# V3.net
KiCad netlist of a schematic drawn in Altium Designer
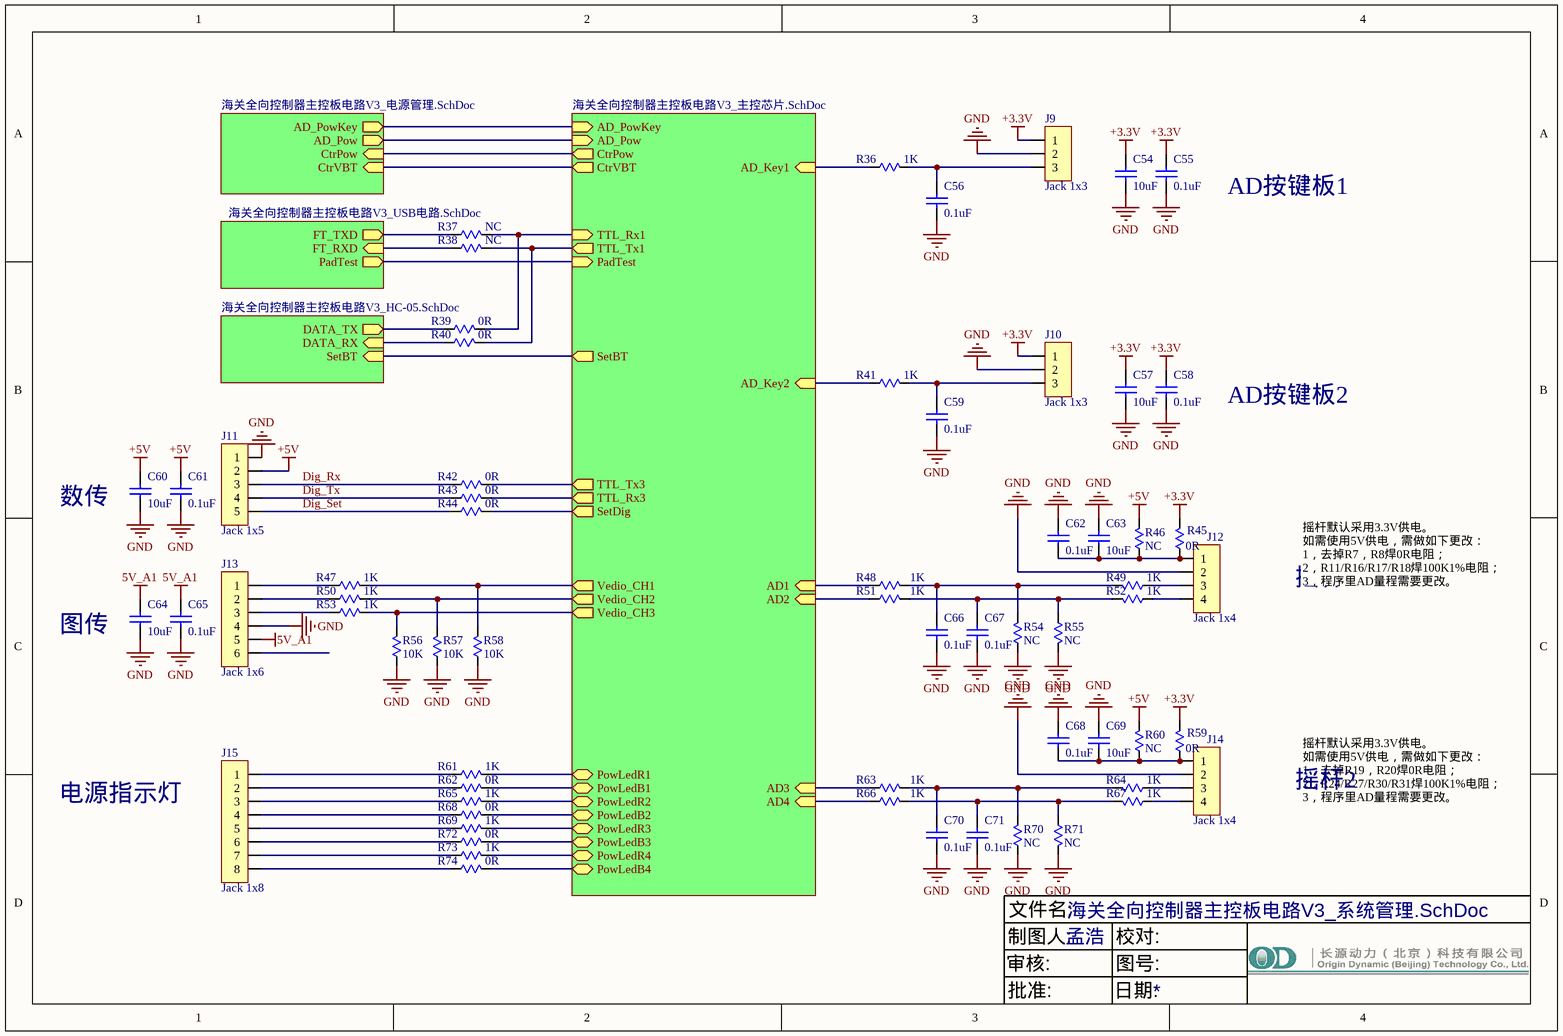
[diagram p0: 海关全向控制器主控板电路V3_系统管理.SchDoc]

(export (version "E")
  (design (tool "Eeschema 10.0.6"))
  (components
    (comp (ref "C54")
      (value "10uF")
      (footprint "C0805")
      (description "Capacitor")
      (fields (field (name "PUBLISHER") "Altium Limited"))
      (libsource (lib "Miscellaneous Devices") (part "Cap"))
    )
    (comp (ref "C55")
      (value "0.1uF")
      (footprint "C0805")
      (description "Capacitor")
      (fields (field (name "PUBLISHER") "Altium Limited"))
      (libsource (lib "Miscellaneous Devices") (part "Cap"))
    )
    (comp (ref "C56")
      (value "0.1uF")
      (footprint "C0805")
      (description "Capacitor")
      (fields (field (name "PUBLISHER") "Altium Limited"))
      (libsource (lib "Miscellaneous Devices") (part "Cap"))
    )
    (comp (ref "C57")
      (value "10uF")
      (footprint "C0805")
      (description "Capacitor")
      (fields (field (name "PUBLISHER") "Altium Limited"))
      (libsource (lib "Miscellaneous Devices") (part "Cap"))
    )
    (comp (ref "C58")
      (value "0.1uF")
      (footprint "C0805")
      (description "Capacitor")
      (fields (field (name "PUBLISHER") "Altium Limited"))
      (libsource (lib "Miscellaneous Devices") (part "Cap"))
    )
    (comp (ref "C59")
      (value "0.1uF")
      (footprint "C0805")
      (description "Capacitor")
      (fields (field (name "PUBLISHER") "Altium Limited"))
      (libsource (lib "Miscellaneous Devices") (part "Cap"))
    )
    (comp (ref "C60")
      (value "10uF")
      (footprint "C0805")
      (description "Capacitor")
      (fields (field (name "PUBLISHER") "Altium Limited"))
      (libsource (lib "Miscellaneous Devices") (part "Cap"))
    )
    (comp (ref "C61")
      (value "0.1uF")
      (footprint "C0805")
      (description "Capacitor")
      (fields (field (name "PUBLISHER") "Altium Limited"))
      (libsource (lib "Miscellaneous Devices") (part "Cap"))
    )
    (comp (ref "C62")
      (value "0.1uF")
      (footprint "C0805")
      (description "Capacitor")
      (fields (field (name "PUBLISHER") "Altium Limited"))
      (libsource (lib "Miscellaneous Devices") (part "Cap"))
    )
    (comp (ref "C63")
      (value "10uF")
      (footprint "C0805")
      (description "Capacitor")
      (fields (field (name "PUBLISHER") "Altium Limited"))
      (libsource (lib "Miscellaneous Devices") (part "Cap"))
    )
    (comp (ref "C64")
      (value "10uF")
      (footprint "C0805")
      (description "Capacitor")
      (fields (field (name "PUBLISHER") "Altium Limited"))
      (libsource (lib "Miscellaneous Devices") (part "Cap"))
    )
    (comp (ref "C65")
      (value "0.1uF")
      (footprint "C0805")
      (description "Capacitor")
      (fields (field (name "PUBLISHER") "Altium Limited"))
      (libsource (lib "Miscellaneous Devices") (part "Cap"))
    )
    (comp (ref "C66")
      (value "0.1uF")
      (footprint "C0805")
      (description "Capacitor")
      (fields (field (name "PUBLISHER") "Altium Limited"))
      (libsource (lib "Miscellaneous Devices") (part "Cap"))
    )
    (comp (ref "C67")
      (value "0.1uF")
      (footprint "C0805")
      (description "Capacitor")
      (fields (field (name "PUBLISHER") "Altium Limited"))
      (libsource (lib "Miscellaneous Devices") (part "Cap"))
    )
    (comp (ref "C68")
      (value "0.1uF")
      (footprint "C0805")
      (description "Capacitor")
      (fields (field (name "PUBLISHER") "Altium Limited"))
      (libsource (lib "Miscellaneous Devices") (part "Cap"))
    )
    (comp (ref "C69")
      (value "10uF")
      (footprint "C0805")
      (description "Capacitor")
      (fields (field (name "PUBLISHER") "Altium Limited"))
      (libsource (lib "Miscellaneous Devices") (part "Cap"))
    )
    (comp (ref "C70")
      (value "0.1uF")
      (footprint "C0805")
      (description "Capacitor")
      (fields (field (name "PUBLISHER") "Altium Limited"))
      (libsource (lib "Miscellaneous Devices") (part "Cap"))
    )
    (comp (ref "C71")
      (value "0.1uF")
      (footprint "C0805")
      (description "Capacitor")
      (fields (field (name "PUBLISHER") "Altium Limited"))
      (libsource (lib "Miscellaneous Devices") (part "Cap"))
    )
    (comp (ref "J9")
      (value "Jack 1x3")
      (footprint "ZH-3AWD")
      (description "插座")
      (libsource (lib "Connector") (part "Jack 1x3"))
    )
    (comp (ref "J10")
      (value "Jack 1x3")
      (footprint "ZH-3AWD")
      (description "插座")
      (libsource (lib "Connector") (part "Jack 1x3"))
    )
    (comp (ref "J11")
      (value "Jack 1x5")
      (footprint "ZH-5AWD")
      (description "插座")
      (libsource (lib "Connector") (part "Jack 1x5"))
    )
    (comp (ref "J12")
      (value "Jack 1x4")
      (footprint "ZH-4AWD")
      (description "插座")
      (libsource (lib "Connector") (part "Jack 1x4"))
    )
    (comp (ref "J13")
      (value "Jack 1x6")
      (footprint "ZH-6AWD")
      (description "插座")
      (libsource (lib "Connector") (part "Jack 1x6"))
    )
    (comp (ref "J14")
      (value "Jack 1x4")
      (footprint "ZH-4AWD")
      (description "插座")
      (libsource (lib "Connector") (part "Jack 1x4"))
    )
    (comp (ref "J15")
      (value "Jack 1x8")
      (footprint "ZH-8AWD")
      (description "插座")
      (libsource (lib "Connector") (part "Jack 1x8"))
    )
    (comp (ref "R36")
      (value "1K")
      (footprint "R0805")
      (description "Resistor")
      (fields (field (name "PUBLISHER") "Altium Limited"))
      (libsource (lib "UP-Robot") (part "Res"))
    )
    (comp (ref "R37")
      (value "NC")
      (footprint "R0805")
      (description "Resistor")
      (fields (field (name "PUBLISHER") "Altium Limited"))
      (libsource (lib "Temp") (part "Res"))
    )
    (comp (ref "R38")
      (value "NC")
      (footprint "R0805")
      (description "Resistor")
      (fields (field (name "PUBLISHER") "Altium Limited"))
      (libsource (lib "Temp") (part "Res"))
    )
    (comp (ref "R39")
      (value "0R")
      (footprint "R0805")
      (description "Resistor")
      (fields (field (name "PUBLISHER") "Altium Limited"))
      (libsource (lib "Temp") (part "Res"))
    )
    (comp (ref "R40")
      (value "0R")
      (footprint "R0805")
      (description "Resistor")
      (fields (field (name "PUBLISHER") "Altium Limited"))
      (libsource (lib "Temp") (part "Res"))
    )
    (comp (ref "R41")
      (value "1K")
      (footprint "R0805")
      (description "Resistor")
      (fields (field (name "PUBLISHER") "Altium Limited"))
      (libsource (lib "UP-Robot") (part "Res"))
    )
    (comp (ref "R42")
      (value "0R")
      (footprint "R0805")
      (description "Resistor")
      (fields (field (name "PUBLISHER") "Altium Limited"))
      (libsource (lib "UP-Robot") (part "Res"))
    )
    (comp (ref "R43")
      (value "0R")
      (footprint "R0805")
      (description "Resistor")
      (fields (field (name "PUBLISHER") "Altium Limited"))
      (libsource (lib "UP-Robot") (part "Res"))
    )
    (comp (ref "R44")
      (value "0R")
      (footprint "R0805")
      (description "Resistor")
      (fields (field (name "PUBLISHER") "Altium Limited"))
      (libsource (lib "UP-Robot") (part "Res"))
    )
    (comp (ref "R45")
      (value "0R")
      (footprint "R0805")
      (description "Resistor")
      (fields (field (name "PUBLISHER") "Altium Limited"))
      (libsource (lib "UP-Robot") (part "Res"))
    )
    (comp (ref "R46")
      (value "NC")
      (footprint "R0805")
      (description "Resistor")
      (fields (field (name "PUBLISHER") "Altium Limited"))
      (libsource (lib "UP-Robot") (part "Res"))
    )
    (comp (ref "R47")
      (value "1K")
      (footprint "R0805")
      (description "Resistor")
      (fields (field (name "PUBLISHER") "Altium Limited"))
      (libsource (lib "UP-Robot") (part "Res"))
    )
    (comp (ref "R48")
      (value "1K")
      (footprint "R0805")
      (description "Resistor")
      (fields (field (name "PUBLISHER") "Altium Limited"))
      (libsource (lib "UP-Robot") (part "Res"))
    )
    (comp (ref "R49")
      (value "1K")
      (footprint "R0805")
      (description "Resistor")
      (fields (field (name "PUBLISHER") "Altium Limited"))
      (libsource (lib "UP-Robot") (part "Res"))
    )
    (comp (ref "R50")
      (value "1K")
      (footprint "R0805")
      (description "Resistor")
      (fields (field (name "PUBLISHER") "Altium Limited"))
      (libsource (lib "UP-Robot") (part "Res"))
    )
    (comp (ref "R51")
      (value "1K")
      (footprint "R0805")
      (description "Resistor")
      (fields (field (name "PUBLISHER") "Altium Limited"))
      (libsource (lib "UP-Robot") (part "Res"))
    )
    (comp (ref "R52")
      (value "1K")
      (footprint "R0805")
      (description "Resistor")
      (fields (field (name "PUBLISHER") "Altium Limited"))
      (libsource (lib "UP-Robot") (part "Res"))
    )
    (comp (ref "R53")
      (value "1K")
      (footprint "R0805")
      (description "Resistor")
      (fields (field (name "PUBLISHER") "Altium Limited"))
      (libsource (lib "UP-Robot") (part "Res"))
    )
    (comp (ref "R54")
      (value "NC")
      (footprint "R0805")
      (description "Resistor")
      (fields (field (name "PUBLISHER") "Altium Limited"))
      (libsource (lib "UP-Robot") (part "Res"))
    )
    (comp (ref "R55")
      (value "NC")
      (footprint "R0805")
      (description "Resistor")
      (fields (field (name "PUBLISHER") "Altium Limited"))
      (libsource (lib "UP-Robot") (part "Res"))
    )
    (comp (ref "R56")
      (value "10K")
      (footprint "R0805")
      (description "Resistor")
      (fields (field (name "PUBLISHER") "Altium Limited"))
      (libsource (lib "UP-Robot") (part "Res"))
    )
    (comp (ref "R57")
      (value "10K")
      (footprint "R0805")
      (description "Resistor")
      (fields (field (name "PUBLISHER") "Altium Limited"))
      (libsource (lib "UP-Robot") (part "Res"))
    )
    (comp (ref "R58")
      (value "10K")
      (footprint "R0805")
      (description "Resistor")
      (fields (field (name "PUBLISHER") "Altium Limited"))
      (libsource (lib "UP-Robot") (part "Res"))
    )
    (comp (ref "R59")
      (value "0R")
      (footprint "R0805")
      (description "Resistor")
      (fields (field (name "PUBLISHER") "Altium Limited"))
      (libsource (lib "UP-Robot") (part "Res"))
    )
    (comp (ref "R60")
      (value "NC")
      (footprint "R0805")
      (description "Resistor")
      (fields (field (name "PUBLISHER") "Altium Limited"))
      (libsource (lib "UP-Robot") (part "Res"))
    )
    (comp (ref "R61")
      (value "1K")
      (footprint "R0805")
      (description "Resistor")
      (fields (field (name "PUBLISHER") "Altium Limited"))
      (libsource (lib "UP-Robot") (part "Res"))
    )
    (comp (ref "R62")
      (value "0R")
      (footprint "R0805")
      (description "Resistor")
      (fields (field (name "PUBLISHER") "Altium Limited"))
      (libsource (lib "UP-Robot") (part "Res"))
    )
    (comp (ref "R63")
      (value "1K")
      (footprint "R0805")
      (description "Resistor")
      (fields (field (name "PUBLISHER") "Altium Limited"))
      (libsource (lib "UP-Robot") (part "Res"))
    )
    (comp (ref "R64")
      (value "1K")
      (footprint "R0805")
      (description "Resistor")
      (fields (field (name "PUBLISHER") "Altium Limited"))
      (libsource (lib "UP-Robot") (part "Res"))
    )
    (comp (ref "R65")
      (value "1K")
      (footprint "R0805")
      (description "Resistor")
      (fields (field (name "PUBLISHER") "Altium Limited"))
      (libsource (lib "UP-Robot") (part "Res"))
    )
    (comp (ref "R66")
      (value "1K")
      (footprint "R0805")
      (description "Resistor")
      (fields (field (name "PUBLISHER") "Altium Limited"))
      (libsource (lib "UP-Robot") (part "Res"))
    )
    (comp (ref "R67")
      (value "1K")
      (footprint "R0805")
      (description "Resistor")
      (fields (field (name "PUBLISHER") "Altium Limited"))
      (libsource (lib "UP-Robot") (part "Res"))
    )
    (comp (ref "R68")
      (value "0R")
      (footprint "R0805")
      (description "Resistor")
      (fields (field (name "PUBLISHER") "Altium Limited"))
      (libsource (lib "UP-Robot") (part "Res"))
    )
    (comp (ref "R69")
      (value "1K")
      (footprint "R0805")
      (description "Resistor")
      (fields (field (name "PUBLISHER") "Altium Limited"))
      (libsource (lib "UP-Robot") (part "Res"))
    )
    (comp (ref "R70")
      (value "NC")
      (footprint "R0805")
      (description "Resistor")
      (fields (field (name "PUBLISHER") "Altium Limited"))
      (libsource (lib "UP-Robot") (part "Res"))
    )
    (comp (ref "R71")
      (value "NC")
      (footprint "R0805")
      (description "Resistor")
      (fields (field (name "PUBLISHER") "Altium Limited"))
      (libsource (lib "UP-Robot") (part "Res"))
    )
    (comp (ref "R72")
      (value "0R")
      (footprint "R0805")
      (description "Resistor")
      (fields (field (name "PUBLISHER") "Altium Limited"))
      (libsource (lib "UP-Robot") (part "Res"))
    )
    (comp (ref "R73")
      (value "1K")
      (footprint "R0805")
      (description "Resistor")
      (fields (field (name "PUBLISHER") "Altium Limited"))
      (libsource (lib "UP-Robot") (part "Res"))
    )
    (comp (ref "R74")
      (value "0R")
      (footprint "R0805")
      (description "Resistor")
      (fields (field (name "PUBLISHER") "Altium Limited"))
      (libsource (lib "UP-Robot") (part "Res"))
    )
  )
  (nets
    (net (code "1") (name "+3.3V") (class "Default")
      (node (ref "C54") (pin "1") (pinfunction "1_1") (pintype "passive"))
      (node (ref "C55") (pin "1") (pinfunction "1_1") (pintype "passive"))
      (node (ref "C57") (pin "1") (pinfunction "1_1") (pintype "passive"))
      (node (ref "C58") (pin "1") (pinfunction "1_1") (pintype "passive"))
      (node (ref "J10") (pin "1") (pinfunction "1_1") (pintype "passive"))
      (node (ref "J9") (pin "1") (pinfunction "1_1") (pintype "passive"))
      (node (ref "R45") (pin "1") (pinfunction "1_1") (pintype "passive"))
      (node (ref "R59") (pin "1") (pinfunction "1_1") (pintype "passive"))
    )
    (net (code "2") (name "+5V") (class "Default")
      (node (ref "C60") (pin "1") (pinfunction "1_1") (pintype "passive"))
      (node (ref "C61") (pin "1") (pinfunction "1_1") (pintype "passive"))
      (node (ref "J11") (pin "2") (pinfunction "2_2") (pintype "passive"))
      (node (ref "R46") (pin "1") (pinfunction "1_1") (pintype "passive"))
      (node (ref "R60") (pin "1") (pinfunction "1_1") (pintype "passive"))
    )
    (net (code "3") (name "/AD1") (class "Default")
      (node (ref "R48") (pin "2") (pinfunction "2_2") (pintype "passive"))
    )
    (net (code "4") (name "/AD2") (class "Default")
      (node (ref "R51") (pin "2") (pinfunction "2_2") (pintype "passive"))
    )
    (net (code "5") (name "/AD3") (class "Default")
      (node (ref "R63") (pin "2") (pinfunction "2_2") (pintype "passive"))
    )
    (net (code "6") (name "/AD4") (class "Default")
      (node (ref "R66") (pin "2") (pinfunction "2_2") (pintype "passive"))
    )
    (net (code "7") (name "/AD_Key1") (class "Default")
      (node (ref "R36") (pin "1") (pinfunction "1_1") (pintype "passive"))
    )
    (net (code "8") (name "/AD_Key2") (class "Default")
      (node (ref "R41") (pin "1") (pinfunction "1_1") (pintype "passive"))
    )
    (net (code "13") (name "/DATA_RX") (class "Default")
      (node (ref "R40") (pin "2") (pinfunction "2_2") (pintype "passive"))
    )
    (net (code "14") (name "/DATA_TX") (class "Default")
      (node (ref "R39") (pin "2") (pinfunction "2_2") (pintype "passive"))
    )
    (net (code "15") (name "/Dig_Rx") (class "Default")
      (node (ref "J11") (pin "3") (pinfunction "3_3") (pintype "passive"))
      (node (ref "R42") (pin "1") (pinfunction "1_1") (pintype "passive"))
    )
    (net (code "16") (name "/Dig_Set") (class "Default")
      (node (ref "J11") (pin "5") (pinfunction "5_5") (pintype "passive"))
      (node (ref "R44") (pin "1") (pinfunction "1_1") (pintype "passive"))
    )
    (net (code "17") (name "/Dig_Tx") (class "Default")
      (node (ref "J11") (pin "4") (pinfunction "4_4") (pintype "passive"))
      (node (ref "R43") (pin "1") (pinfunction "1_1") (pintype "passive"))
    )
    (net (code "18") (name "/FT_RXD") (class "Default")
      (node (ref "R38") (pin "2") (pinfunction "2_2") (pintype "passive"))
    )
    (net (code "19") (name "/FT_TXD") (class "Default")
      (node (ref "R37") (pin "2") (pinfunction "2_2") (pintype "passive"))
    )
    (net (code "21") (name "/PowLedB1") (class "Default")
      (node (ref "R62") (pin "2") (pinfunction "2_2") (pintype "passive"))
    )
    (net (code "22") (name "/PowLedB2") (class "Default")
      (node (ref "R68") (pin "2") (pinfunction "2_2") (pintype "passive"))
    )
    (net (code "23") (name "/PowLedB3") (class "Default")
      (node (ref "R72") (pin "2") (pinfunction "2_2") (pintype "passive"))
    )
    (net (code "24") (name "/PowLedB4") (class "Default")
      (node (ref "R74") (pin "2") (pinfunction "2_2") (pintype "passive"))
    )
    (net (code "25") (name "/PowLedR1") (class "Default")
      (node (ref "R61") (pin "2") (pinfunction "2_2") (pintype "passive"))
    )
    (net (code "26") (name "/PowLedR2") (class "Default")
      (node (ref "R65") (pin "2") (pinfunction "2_2") (pintype "passive"))
    )
    (net (code "27") (name "/PowLedR3") (class "Default")
      (node (ref "R69") (pin "2") (pinfunction "2_2") (pintype "passive"))
    )
    (net (code "28") (name "/PowLedR4") (class "Default")
      (node (ref "R73") (pin "2") (pinfunction "2_2") (pintype "passive"))
    )
    (net (code "30") (name "/SetDig") (class "Default")
      (node (ref "R44") (pin "2") (pinfunction "2_2") (pintype "passive"))
    )
    (net (code "31") (name "/TTL_Rx1") (class "Default")
      (node (ref "R37") (pin "1") (pinfunction "1_1") (pintype "passive"))
      (node (ref "R39") (pin "1") (pinfunction "1_1") (pintype "passive"))
    )
    (net (code "32") (name "/TTL_Rx3") (class "Default")
      (node (ref "R43") (pin "2") (pinfunction "2_2") (pintype "passive"))
    )
    (net (code "33") (name "/TTL_Tx1") (class "Default")
      (node (ref "R38") (pin "1") (pinfunction "1_1") (pintype "passive"))
      (node (ref "R40") (pin "1") (pinfunction "1_1") (pintype "passive"))
    )
    (net (code "34") (name "/TTL_Tx3") (class "Default")
      (node (ref "R42") (pin "2") (pinfunction "2_2") (pintype "passive"))
    )
    (net (code "35") (name "/Vedio_CH1") (class "Default")
      (node (ref "R47") (pin "2") (pinfunction "2_2") (pintype "passive"))
      (node (ref "R58") (pin "2") (pinfunction "2_2") (pintype "passive"))
    )
    (net (code "36") (name "/Vedio_CH2") (class "Default")
      (node (ref "R50") (pin "2") (pinfunction "2_2") (pintype "passive"))
      (node (ref "R57") (pin "2") (pinfunction "2_2") (pintype "passive"))
    )
    (net (code "37") (name "/Vedio_CH3") (class "Default")
      (node (ref "R53") (pin "2") (pinfunction "2_2") (pintype "passive"))
      (node (ref "R56") (pin "2") (pinfunction "2_2") (pintype "passive"))
    )
    (net (code "38") (name "5V_A1") (class "Default")
      (node (ref "C64") (pin "1") (pinfunction "1_1") (pintype "passive"))
      (node (ref "C65") (pin "1") (pinfunction "1_1") (pintype "passive"))
      (node (ref "J13") (pin "5") (pinfunction "5_5") (pintype "passive"))
    )
    (net (code "39") (name "GND") (class "Default")
      (node (ref "C54") (pin "2") (pinfunction "2_2") (pintype "passive"))
      (node (ref "C55") (pin "2") (pinfunction "2_2") (pintype "passive"))
      (node (ref "C56") (pin "2") (pinfunction "2_2") (pintype "passive"))
      (node (ref "C57") (pin "2") (pinfunction "2_2") (pintype "passive"))
      (node (ref "C58") (pin "2") (pinfunction "2_2") (pintype "passive"))
      (node (ref "C59") (pin "2") (pinfunction "2_2") (pintype "passive"))
      (node (ref "C60") (pin "2") (pinfunction "2_2") (pintype "passive"))
      (node (ref "C61") (pin "2") (pinfunction "2_2") (pintype "passive"))
      (node (ref "C62") (pin "1") (pinfunction "1_1") (pintype "passive"))
      (node (ref "C63") (pin "1") (pinfunction "1_1") (pintype "passive"))
      (node (ref "C64") (pin "2") (pinfunction "2_2") (pintype "passive"))
      (node (ref "C65") (pin "2") (pinfunction "2_2") (pintype "passive"))
      (node (ref "C66") (pin "2") (pinfunction "2_2") (pintype "passive"))
      (node (ref "C67") (pin "2") (pinfunction "2_2") (pintype "passive"))
      (node (ref "C68") (pin "1") (pinfunction "1_1") (pintype "passive"))
      (node (ref "C69") (pin "1") (pinfunction "1_1") (pintype "passive"))
      (node (ref "C70") (pin "2") (pinfunction "2_2") (pintype "passive"))
      (node (ref "C71") (pin "2") (pinfunction "2_2") (pintype "passive"))
      (node (ref "J10") (pin "2") (pinfunction "2_2") (pintype "passive"))
      (node (ref "J11") (pin "1") (pinfunction "1_1") (pintype "passive"))
      (node (ref "J12") (pin "2") (pinfunction "2_2") (pintype "passive"))
      (node (ref "J13") (pin "4") (pinfunction "4_4") (pintype "passive"))
      (node (ref "J14") (pin "2") (pinfunction "2_2") (pintype "passive"))
      (node (ref "J9") (pin "2") (pinfunction "2_2") (pintype "passive"))
      (node (ref "R54") (pin "2") (pinfunction "2_2") (pintype "passive"))
      (node (ref "R55") (pin "1") (pinfunction "1_1") (pintype "passive"))
      (node (ref "R56") (pin "1") (pinfunction "1_1") (pintype "passive"))
      (node (ref "R57") (pin "1") (pinfunction "1_1") (pintype "passive"))
      (node (ref "R58") (pin "1") (pinfunction "1_1") (pintype "passive"))
      (node (ref "R70") (pin "2") (pinfunction "2_2") (pintype "passive"))
      (node (ref "R71") (pin "1") (pinfunction "1_1") (pintype "passive"))
    )
    (net (code "40") (name "Net-(C56-Pad1)") (class "Default")
      (node (ref "C56") (pin "1") (pinfunction "1_1") (pintype "passive"))
      (node (ref "J9") (pin "3") (pinfunction "3_3") (pintype "passive"))
      (node (ref "R36") (pin "2") (pinfunction "2_2") (pintype "passive"))
    )
    (net (code "41") (name "Net-(C59-Pad1)") (class "Default")
      (node (ref "C59") (pin "1") (pinfunction "1_1") (pintype "passive"))
      (node (ref "J10") (pin "3") (pinfunction "3_3") (pintype "passive"))
      (node (ref "R41") (pin "2") (pinfunction "2_2") (pintype "passive"))
    )
    (net (code "42") (name "Net-(C62-Pad2)") (class "Default")
      (node (ref "C62") (pin "2") (pinfunction "2_2") (pintype "passive"))
      (node (ref "C63") (pin "2") (pinfunction "2_2") (pintype "passive"))
      (node (ref "J12") (pin "1") (pinfunction "1_1") (pintype "passive"))
      (node (ref "R45") (pin "2") (pinfunction "2_2") (pintype "passive"))
      (node (ref "R46") (pin "2") (pinfunction "2_2") (pintype "passive"))
    )
    (net (code "43") (name "Net-(C66-Pad1)") (class "Default")
      (node (ref "C66") (pin "1") (pinfunction "1_1") (pintype "passive"))
      (node (ref "R48") (pin "1") (pinfunction "1_1") (pintype "passive"))
      (node (ref "R49") (pin "1") (pinfunction "1_1") (pintype "passive"))
      (node (ref "R54") (pin "1") (pinfunction "1_1") (pintype "passive"))
    )
    (net (code "44") (name "Net-(C67-Pad1)") (class "Default")
      (node (ref "C67") (pin "1") (pinfunction "1_1") (pintype "passive"))
      (node (ref "R51") (pin "1") (pinfunction "1_1") (pintype "passive"))
      (node (ref "R52") (pin "1") (pinfunction "1_1") (pintype "passive"))
      (node (ref "R55") (pin "2") (pinfunction "2_2") (pintype "passive"))
    )
    (net (code "45") (name "Net-(C68-Pad2)") (class "Default")
      (node (ref "C68") (pin "2") (pinfunction "2_2") (pintype "passive"))
      (node (ref "C69") (pin "2") (pinfunction "2_2") (pintype "passive"))
      (node (ref "J14") (pin "1") (pinfunction "1_1") (pintype "passive"))
      (node (ref "R59") (pin "2") (pinfunction "2_2") (pintype "passive"))
      (node (ref "R60") (pin "2") (pinfunction "2_2") (pintype "passive"))
    )
    (net (code "46") (name "Net-(C70-Pad1)") (class "Default")
      (node (ref "C70") (pin "1") (pinfunction "1_1") (pintype "passive"))
      (node (ref "R63") (pin "1") (pinfunction "1_1") (pintype "passive"))
      (node (ref "R64") (pin "1") (pinfunction "1_1") (pintype "passive"))
      (node (ref "R70") (pin "1") (pinfunction "1_1") (pintype "passive"))
    )
    (net (code "47") (name "Net-(C71-Pad1)") (class "Default")
      (node (ref "C71") (pin "1") (pinfunction "1_1") (pintype "passive"))
      (node (ref "R66") (pin "1") (pinfunction "1_1") (pintype "passive"))
      (node (ref "R67") (pin "1") (pinfunction "1_1") (pintype "passive"))
      (node (ref "R71") (pin "2") (pinfunction "2_2") (pintype "passive"))
    )
    (net (code "48") (name "Net-(J12-Pad3)") (class "Default")
      (node (ref "J12") (pin "3") (pinfunction "3_3") (pintype "passive"))
      (node (ref "R49") (pin "2") (pinfunction "2_2") (pintype "passive"))
    )
    (net (code "49") (name "Net-(J12-Pad4)") (class "Default")
      (node (ref "J12") (pin "4") (pinfunction "4_4") (pintype "passive"))
      (node (ref "R52") (pin "2") (pinfunction "2_2") (pintype "passive"))
    )
    (net (code "50") (name "Net-(J13-Pad1)") (class "Default")
      (node (ref "J13") (pin "1") (pinfunction "1_1") (pintype "passive"))
      (node (ref "R47") (pin "1") (pinfunction "1_1") (pintype "passive"))
    )
    (net (code "51") (name "Net-(J13-Pad2)") (class "Default")
      (node (ref "J13") (pin "2") (pinfunction "2_2") (pintype "passive"))
      (node (ref "R50") (pin "1") (pinfunction "1_1") (pintype "passive"))
    )
    (net (code "52") (name "Net-(J13-Pad3)") (class "Default")
      (node (ref "J13") (pin "3") (pinfunction "3_3") (pintype "passive"))
      (node (ref "R53") (pin "1") (pinfunction "1_1") (pintype "passive"))
    )
    (net (code "53") (name "Net-(J14-Pad3)") (class "Default")
      (node (ref "J14") (pin "3") (pinfunction "3_3") (pintype "passive"))
      (node (ref "R64") (pin "2") (pinfunction "2_2") (pintype "passive"))
    )
    (net (code "54") (name "Net-(J14-Pad4)") (class "Default")
      (node (ref "J14") (pin "4") (pinfunction "4_4") (pintype "passive"))
      (node (ref "R67") (pin "2") (pinfunction "2_2") (pintype "passive"))
    )
    (net (code "55") (name "Net-(J15-Pad1)") (class "Default")
      (node (ref "J15") (pin "1") (pinfunction "1_1") (pintype "passive"))
      (node (ref "R61") (pin "1") (pinfunction "1_1") (pintype "passive"))
    )
    (net (code "56") (name "Net-(J15-Pad2)") (class "Default")
      (node (ref "J15") (pin "2") (pinfunction "2_2") (pintype "passive"))
      (node (ref "R62") (pin "1") (pinfunction "1_1") (pintype "passive"))
    )
    (net (code "57") (name "Net-(J15-Pad3)") (class "Default")
      (node (ref "J15") (pin "3") (pinfunction "3_3") (pintype "passive"))
      (node (ref "R65") (pin "1") (pinfunction "1_1") (pintype "passive"))
    )
    (net (code "58") (name "Net-(J15-Pad4)") (class "Default")
      (node (ref "J15") (pin "4") (pinfunction "4_4") (pintype "passive"))
      (node (ref "R68") (pin "1") (pinfunction "1_1") (pintype "passive"))
    )
    (net (code "59") (name "Net-(J15-Pad5)") (class "Default")
      (node (ref "J15") (pin "5") (pinfunction "5_5") (pintype "passive"))
      (node (ref "R69") (pin "1") (pinfunction "1_1") (pintype "passive"))
    )
    (net (code "60") (name "Net-(J15-Pad6)") (class "Default")
      (node (ref "J15") (pin "6") (pinfunction "6_6") (pintype "passive"))
      (node (ref "R72") (pin "1") (pinfunction "1_1") (pintype "passive"))
    )
    (net (code "61") (name "Net-(J15-Pad7)") (class "Default")
      (node (ref "J15") (pin "7") (pinfunction "7_7") (pintype "passive"))
      (node (ref "R73") (pin "1") (pinfunction "1_1") (pintype "passive"))
    )
    (net (code "62") (name "Net-(J15-Pad8)") (class "Default")
      (node (ref "J15") (pin "8") (pinfunction "8_8") (pintype "passive"))
      (node (ref "R74") (pin "1") (pinfunction "1_1") (pintype "passive"))
    )
    (net (code "63") (name "unconnected-(J13-Pad6)") (class "Default")
      (node (ref "J13") (pin "6") (pinfunction "6_6") (pintype "passive"))
    )
  )
)
